# MCU.net
KiCad netlist of a schematic drawn in Altium Designer
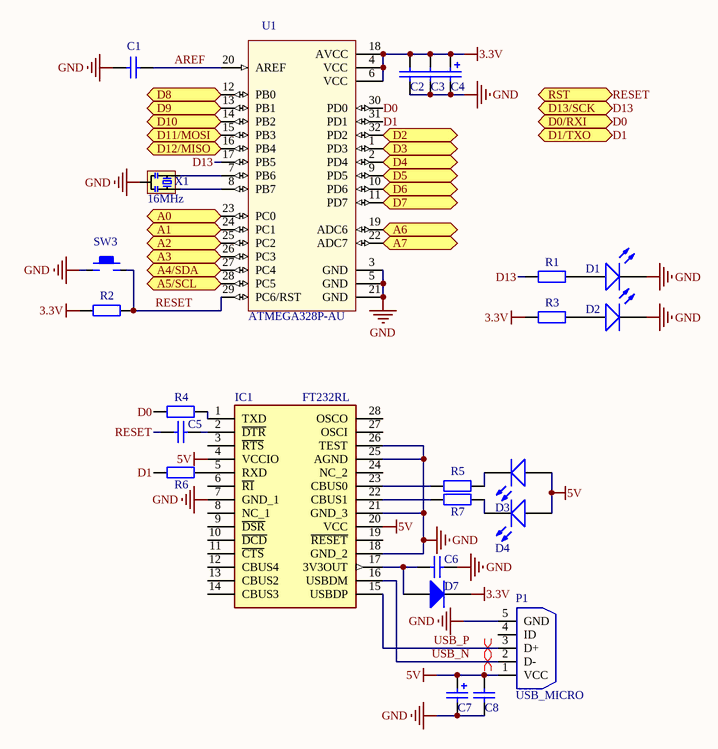
[diagram p0: MCU.SchDoc]

(export (version "E")
  (design (tool "Eeschema 10.0.6"))
  (components
    (comp (ref "C1")
      (value "100nF")
      (footprint "CAP-0603")
      (description "贴片电容")
      (libsource (lib "Power_Lib_Altium") (part "CAP"))
    )
    (comp (ref "C2")
      (value "1uF")
      (footprint "CAP-0603")
      (description "贴片电容")
      (libsource (lib "Power_Lib_Altium") (part "CAP"))
    )
    (comp (ref "C3")
      (value "1uF")
      (footprint "CAP-0603")
      (description "贴片电容")
      (libsource (lib "Power_Lib_Altium") (part "CAP"))
    )
    (comp (ref "C4")
      (value "4.7uF 16V")
      (footprint "CAP-AUX-3216")
      (description "贴片电容-有极性")
      (libsource (lib "Power_Lib_Altium") (part "CAP-POL"))
    )
    (comp (ref "C5")
      (value "100nF")
      (footprint "CAP-0603")
      (description "贴片电容")
      (libsource (lib "Power_Lib_Altium") (part "CAP"))
    )
    (comp (ref "C6")
      (value "100nF")
      (footprint "CAP-0603")
      (description "贴片电容")
      (libsource (lib "Power_Lib_Altium") (part "CAP"))
    )
    (comp (ref "C7")
      (value "4.7uF 16V")
      (footprint "CAP-AUX-3216")
      (description "贴片电容-有极性")
      (libsource (lib "Power_Lib_Altium") (part "CAP-POL"))
    )
    (comp (ref "C8")
      (value "100nF")
      (footprint "CAP-0603")
      (description "贴片电容")
      (libsource (lib "Power_Lib_Altium") (part "CAP"))
    )
    (comp (ref "D1")
      (value "GREEN")
      (footprint "LED-0603")
      (description "发光二极管")
      (libsource (lib "Power_Lib_Altium") (part "LED"))
    )
    (comp (ref "D2")
      (value "RED")
      (footprint "LED-0603")
      (description "发光二极管")
      (libsource (lib "Power_Lib_Altium") (part "LED"))
    )
    (comp (ref "D3")
      (value "RED")
      (footprint "LED-0603")
      (description "发光二极管")
      (libsource (lib "Power_Lib_Altium") (part "LED"))
    )
    (comp (ref "D4")
      (value "RED")
      (footprint "LED-0603")
      (description "发光二极管")
      (libsource (lib "Power_Lib_Altium") (part "LED"))
    )
    (comp (ref "D7")
      (value "SS14")
      (footprint "SOD_123")
      (description "二极管")
      (libsource (lib "Power_Lib_Altium") (part "DIODE"))
    )
    (comp (ref "IC1")
      (value "FT232RL")
      (footprint "SSOP")
      (description "USB to UART")
      (fields (field (name "RS PART NUMBER") "0406580P"))
      (libsource (lib "Power_Lib_Altium") (part "FT232RL"))
    )
    (comp (ref "P1")
      (value "USB_MICRO")
      (footprint "Micro usb座 -全贴片")
      (description "USB 接口")
      (libsource (lib "Power_Lib_Altium") (part "USB_MICRO"))
    )
    (comp (ref "R1")
      (value "330R")
      (footprint "R-0603")
      (description "贴片电阻")
      (libsource (lib "Power_Lib_Altium") (part "RES"))
    )
    (comp (ref "R2")
      (value "1K")
      (footprint "R-0603")
      (description "贴片电阻")
      (libsource (lib "Power_Lib_Altium") (part "RES"))
    )
    (comp (ref "R3")
      (value "10K")
      (footprint "R-0603")
      (description "贴片电阻")
      (libsource (lib "Power_Lib_Altium") (part "RES"))
    )
    (comp (ref "R4")
      (value "1K")
      (footprint "R-0603")
      (description "贴片电阻")
      (libsource (lib "Power_Lib_Altium") (part "RES"))
    )
    (comp (ref "R5")
      (value "1K")
      (footprint "R-0603")
      (description "贴片电阻")
      (libsource (lib "Power_Lib_Altium") (part "RES"))
    )
    (comp (ref "R6")
      (value "1K")
      (footprint "R-0603")
      (description "贴片电阻")
      (libsource (lib "Power_Lib_Altium") (part "RES"))
    )
    (comp (ref "R7")
      (value "1K")
      (footprint "R-0603")
      (description "贴片电阻")
      (libsource (lib "Power_Lib_Altium") (part "RES"))
    )
    (comp (ref "SW3")
      (value "KEY")
      (footprint "KEY-4P-4.2*3.4*2.5")
      (description "按键开关")
      (libsource (lib "Power_Lib_Altium") (part "KEY"))
    )
    (comp (ref "U1")
      (value "ATMEGA328P-AU")
      (footprint "TQFP-32_7x7x08P")
      (description "微控制器, 8 Bit, Atmega, 20mhz, Tqfp-32")
      (fields (field (name "MF") "Microchip"))
      (libsource (lib "Power_Lib_Altium") (part "ATMEGA328P-AU"))
    )
    (comp (ref "X1")
      (value "16MHz")
      (footprint "CSTCE_G(A)村田晶振")
      (description "有源晶振")
      (libsource (lib "Power_Lib_Altium") (part "XTAL"))
    )
  )
  (nets
    (net (code "1") (name "/A0") (class "Default")
      (node (ref "U1") (pin "23") (pinfunction "PC0_23") (pintype "bidirectional"))
    )
    (net (code "2") (name "/A1") (class "Default")
      (node (ref "U1") (pin "24") (pinfunction "PC1_24") (pintype "bidirectional"))
    )
    (net (code "3") (name "/A2") (class "Default")
      (node (ref "U1") (pin "25") (pinfunction "PC2_25") (pintype "bidirectional"))
    )
    (net (code "4") (name "/A3") (class "Default")
      (node (ref "U1") (pin "26") (pinfunction "PC3_26") (pintype "bidirectional"))
    )
    (net (code "5") (name "/A4{slash}SDA") (class "Default")
      (node (ref "U1") (pin "27") (pinfunction "PC4_27") (pintype "bidirectional"))
    )
    (net (code "6") (name "/A5{slash}SCL") (class "Default")
      (node (ref "U1") (pin "28") (pinfunction "PC5_28") (pintype "bidirectional"))
    )
    (net (code "7") (name "/A6") (class "Default")
      (node (ref "U1") (pin "19") (pinfunction "ADC6_19") (pintype "bidirectional"))
    )
    (net (code "8") (name "/A7") (class "Default")
      (node (ref "U1") (pin "22") (pinfunction "ADC7_22") (pintype "bidirectional"))
    )
    (net (code "9") (name "/AREF") (class "Default")
      (node (ref "C1") (pin "2") (pinfunction "2_2") (pintype "passive"))
      (node (ref "U1") (pin "20") (pinfunction "AREF_20") (pintype "input"))
    )
    (net (code "10") (name "/D0") (class "Default")
      (node (ref "R4") (pin "1") (pinfunction "1_1") (pintype "passive"))
      (node (ref "U1") (pin "30") (pinfunction "PD0_30") (pintype "bidirectional"))
    )
    (net (code "11") (name "/D1") (class "Default")
      (node (ref "R6") (pin "1") (pinfunction "1_1") (pintype "passive"))
      (node (ref "U1") (pin "31") (pinfunction "PD1_31") (pintype "bidirectional"))
    )
    (net (code "12") (name "/D2") (class "Default")
      (node (ref "U1") (pin "32") (pinfunction "PD2_32") (pintype "bidirectional"))
    )
    (net (code "13") (name "/D3") (class "Default")
      (node (ref "U1") (pin "1") (pinfunction "PD3_1") (pintype "bidirectional"))
    )
    (net (code "14") (name "/D4") (class "Default")
      (node (ref "U1") (pin "2") (pinfunction "PD4_2") (pintype "bidirectional"))
    )
    (net (code "15") (name "/D5") (class "Default")
      (node (ref "U1") (pin "9") (pinfunction "PD5_9") (pintype "bidirectional"))
    )
    (net (code "16") (name "/D6") (class "Default")
      (node (ref "U1") (pin "10") (pinfunction "PD6_10") (pintype "bidirectional"))
    )
    (net (code "17") (name "/D7") (class "Default")
      (node (ref "U1") (pin "11") (pinfunction "PD7_11") (pintype "bidirectional"))
    )
    (net (code "18") (name "/D8") (class "Default")
      (node (ref "U1") (pin "12") (pinfunction "PB0_12") (pintype "bidirectional"))
    )
    (net (code "19") (name "/D9") (class "Default")
      (node (ref "U1") (pin "13") (pinfunction "PB1_13") (pintype "bidirectional"))
    )
    (net (code "20") (name "/D10") (class "Default")
      (node (ref "U1") (pin "14") (pinfunction "PB2_14") (pintype "bidirectional"))
    )
    (net (code "21") (name "/D11{slash}MOSI") (class "Default")
      (node (ref "U1") (pin "15") (pinfunction "PB3_15") (pintype "bidirectional"))
    )
    (net (code "22") (name "/D12{slash}MISO") (class "Default")
      (node (ref "U1") (pin "16") (pinfunction "PB4_16") (pintype "bidirectional"))
    )
    (net (code "23") (name "/D13") (class "Default")
      (node (ref "R1") (pin "1") (pinfunction "1_1") (pintype "passive"))
      (node (ref "U1") (pin "17") (pinfunction "PB5_17") (pintype "bidirectional"))
    )
    (net (code "24") (name "/RESET") (class "Default")
      (node (ref "C5") (pin "2") (pinfunction "2_2") (pintype "passive"))
      (node (ref "R2") (pin "2") (pinfunction "2_2") (pintype "passive"))
      (node (ref "SW3") (pin "2") (pinfunction "2_2") (pintype "passive"))
      (node (ref "U1") (pin "29") (pinfunction "PC6/RST_29") (pintype "bidirectional"))
    )
    (net (code "25") (name "/USB_N") (class "Default")
      (node (ref "IC1") (pin "16") (pinfunction "USBDM_16") (pintype "passive"))
      (node (ref "P1") (pin "2") (pinfunction "D-_2") (pintype "passive"))
    )
    (net (code "26") (name "/USB_P") (class "Default")
      (node (ref "IC1") (pin "15") (pinfunction "USBDP_15") (pintype "passive"))
      (node (ref "P1") (pin "3") (pinfunction "D+_3") (pintype "passive"))
    )
    (net (code "27") (name "3.3V") (class "Default")
      (node (ref "C2") (pin "2") (pinfunction "2_2") (pintype "passive"))
      (node (ref "C3") (pin "2") (pinfunction "2_2") (pintype "passive"))
      (node (ref "C4") (pin "1") (pinfunction "1_1") (pintype "passive"))
      (node (ref "D7") (pin "2") (pinfunction "K_2") (pintype "passive"))
      (node (ref "R2") (pin "1") (pinfunction "1_1") (pintype "passive"))
      (node (ref "R3") (pin "1") (pinfunction "1_1") (pintype "passive"))
      (node (ref "U1") (pin "18") (pinfunction "AVCC_18") (pintype "power_in"))
      (node (ref "U1") (pin "4") (pinfunction "VCC_4") (pintype "power_in"))
      (node (ref "U1") (pin "6") (pinfunction "VCC_6") (pintype "power_in"))
    )
    (net (code "28") (name "5V") (class "Default")
      (node (ref "C7") (pin "1") (pinfunction "1_1") (pintype "passive"))
      (node (ref "C8") (pin "2") (pinfunction "2_2") (pintype "passive"))
      (node (ref "D3") (pin "A") (pinfunction "A_A") (pintype "passive"))
      (node (ref "D4") (pin "A") (pinfunction "A_A") (pintype "passive"))
      (node (ref "IC1") (pin "20") (pinfunction "VCC_20") (pintype "power_in"))
      (node (ref "IC1") (pin "4") (pinfunction "VCCIO_4") (pintype "power_in"))
      (node (ref "P1") (pin "1") (pinfunction "VCC_1") (pintype "passive"))
    )
    (net (code "29") (name "GND") (class "Default")
      (node (ref "C1") (pin "1") (pinfunction "1_1") (pintype "passive"))
      (node (ref "C2") (pin "1") (pinfunction "1_1") (pintype "passive"))
      (node (ref "C3") (pin "1") (pinfunction "1_1") (pintype "passive"))
      (node (ref "C4") (pin "2") (pinfunction "2_2") (pintype "passive"))
      (node (ref "C6") (pin "1") (pinfunction "1_1") (pintype "passive"))
      (node (ref "C7") (pin "2") (pinfunction "2_2") (pintype "passive"))
      (node (ref "C8") (pin "1") (pinfunction "1_1") (pintype "passive"))
      (node (ref "D1") (pin "K") (pinfunction "K_K") (pintype "passive"))
      (node (ref "D2") (pin "K") (pinfunction "K_K") (pintype "passive"))
      (node (ref "IC1") (pin "18") (pinfunction "GND_2_18") (pintype "power_in"))
      (node (ref "IC1") (pin "21") (pinfunction "GND_3_21") (pintype "power_in"))
      (node (ref "IC1") (pin "25") (pinfunction "AGND_25") (pintype "power_in"))
      (node (ref "IC1") (pin "26") (pinfunction "TEST_26") (pintype "passive"))
      (node (ref "IC1") (pin "7") (pinfunction "GND_1_7") (pintype "power_in"))
      (node (ref "P1") (pin "5") (pinfunction "GND_5") (pintype "passive"))
      (node (ref "SW3") (pin "1") (pinfunction "1_1") (pintype "passive"))
      (node (ref "U1") (pin "21") (pinfunction "GND_21") (pintype "power_in"))
      (node (ref "U1") (pin "3") (pinfunction "GND_3") (pintype "power_in"))
      (node (ref "U1") (pin "5") (pinfunction "GND_5") (pintype "power_in"))
      (node (ref "X1") (pin "2") (pinfunction "GND_2") (pintype "passive"))
    )
    (net (code "30") (name "Net-(D1-PadA)") (class "Default")
      (node (ref "D1") (pin "A") (pinfunction "A_A") (pintype "passive"))
      (node (ref "R1") (pin "2") (pinfunction "2_2") (pintype "passive"))
    )
    (net (code "31") (name "Net-(D2-PadA)") (class "Default")
      (node (ref "D2") (pin "A") (pinfunction "A_A") (pintype "passive"))
      (node (ref "R3") (pin "2") (pinfunction "2_2") (pintype "passive"))
    )
    (net (code "32") (name "Net-(D3-PadK)") (class "Default")
      (node (ref "D3") (pin "K") (pinfunction "K_K") (pintype "passive"))
      (node (ref "R5") (pin "2") (pinfunction "2_2") (pintype "passive"))
    )
    (net (code "33") (name "Net-(D4-PadK)") (class "Default")
      (node (ref "D4") (pin "K") (pinfunction "K_K") (pintype "passive"))
      (node (ref "R7") (pin "2") (pinfunction "2_2") (pintype "passive"))
    )
    (net (code "34") (name "Net-(D7-A)") (class "Default")
      (node (ref "C6") (pin "2") (pinfunction "2_2") (pintype "passive"))
      (node (ref "D7") (pin "1") (pinfunction "A_1") (pintype "passive"))
      (node (ref "IC1") (pin "17") (pinfunction "3V3OUT_17") (pintype "output"))
    )
    (net (code "35") (name "Net-(IC1-CBUS0)") (class "Default")
      (node (ref "IC1") (pin "23") (pinfunction "CBUS0_23") (pintype "passive"))
      (node (ref "R5") (pin "1") (pinfunction "1_1") (pintype "passive"))
    )
    (net (code "36") (name "Net-(IC1-CBUS1)") (class "Default")
      (node (ref "IC1") (pin "22") (pinfunction "CBUS1_22") (pintype "passive"))
      (node (ref "R7") (pin "1") (pinfunction "1_1") (pintype "passive"))
    )
    (net (code "37") (name "Net-(IC1-RXD)") (class "Default")
      (node (ref "IC1") (pin "5") (pinfunction "RXD_5") (pintype "passive"))
      (node (ref "R6") (pin "2") (pinfunction "2_2") (pintype "passive"))
    )
    (net (code "38") (name "Net-(IC1-TXD)") (class "Default")
      (node (ref "IC1") (pin "1") (pinfunction "TXD_1") (pintype "passive"))
      (node (ref "R4") (pin "2") (pinfunction "2_2") (pintype "passive"))
    )
    (net (code "39") (name "Net-(IC1-~{DTR})") (class "Default")
      (node (ref "C5") (pin "1") (pinfunction "1_1") (pintype "passive"))
      (node (ref "IC1") (pin "2") (pinfunction "~{DTR}_2") (pintype "passive"))
    )
    (net (code "40") (name "Net-(U1-PB6)") (class "Default")
      (node (ref "U1") (pin "7") (pinfunction "PB6_7") (pintype "bidirectional"))
      (node (ref "X1") (pin "1") (pinfunction "OSC1_1") (pintype "passive"))
    )
    (net (code "41") (name "Net-(U1-PB7)") (class "Default")
      (node (ref "U1") (pin "8") (pinfunction "PB7_8") (pintype "bidirectional"))
      (node (ref "X1") (pin "3") (pinfunction "OSC2_3") (pintype "passive"))
    )
    (net (code "42") (name "unconnected-(IC1-CBUS2-Pad13)") (class "Default")
      (node (ref "IC1") (pin "13") (pinfunction "CBUS2_13") (pintype "passive"))
    )
    (net (code "43") (name "unconnected-(IC1-CBUS3-Pad14)") (class "Default")
      (node (ref "IC1") (pin "14") (pinfunction "CBUS3_14") (pintype "passive"))
    )
    (net (code "44") (name "unconnected-(IC1-CBUS4-Pad12)") (class "Default")
      (node (ref "IC1") (pin "12") (pinfunction "CBUS4_12") (pintype "passive"))
    )
    (net (code "45") (name "unconnected-(IC1-NC_1-Pad8)") (class "Default")
      (node (ref "IC1") (pin "8") (pinfunction "NC_1_8") (pintype "passive"))
    )
    (net (code "46") (name "unconnected-(IC1-NC_2-Pad24)") (class "Default")
      (node (ref "IC1") (pin "24") (pinfunction "NC_2_24") (pintype "passive"))
    )
    (net (code "47") (name "unconnected-(IC1-OSCI-Pad27)") (class "Default")
      (node (ref "IC1") (pin "27") (pinfunction "OSCI_27") (pintype "passive"))
    )
    (net (code "48") (name "unconnected-(IC1-OSCO-Pad28)") (class "Default")
      (node (ref "IC1") (pin "28") (pinfunction "OSCO_28") (pintype "passive"))
    )
    (net (code "49") (name "unconnected-(IC1-~{CTS}-Pad11)") (class "Default")
      (node (ref "IC1") (pin "11") (pinfunction "~{CTS}_11") (pintype "passive"))
    )
    (net (code "50") (name "unconnected-(IC1-~{DCD}-Pad10)") (class "Default")
      (node (ref "IC1") (pin "10") (pinfunction "~{DCD}_10") (pintype "passive"))
    )
    (net (code "51") (name "unconnected-(IC1-~{DSR}-Pad9)") (class "Default")
      (node (ref "IC1") (pin "9") (pinfunction "~{DSR}_9") (pintype "passive"))
    )
    (net (code "52") (name "unconnected-(IC1-~{RESET}-Pad19)") (class "Default")
      (node (ref "IC1") (pin "19") (pinfunction "~{RESET}_19") (pintype "passive"))
    )
    (net (code "53") (name "unconnected-(IC1-~{RI}-Pad6)") (class "Default")
      (node (ref "IC1") (pin "6") (pinfunction "~{RI}_6") (pintype "passive"))
    )
    (net (code "54") (name "unconnected-(IC1-~{RTS}-Pad3)") (class "Default")
      (node (ref "IC1") (pin "3") (pinfunction "~{RTS}_3") (pintype "passive"))
    )
    (net (code "55") (name "unconnected-(P1-ID-Pad4)") (class "Default")
      (node (ref "P1") (pin "4") (pinfunction "ID_4") (pintype "passive"))
    )
  )
)
